# ui-jetson-nano.net
KiCad netlist of a schematic drawn in Altium Designer
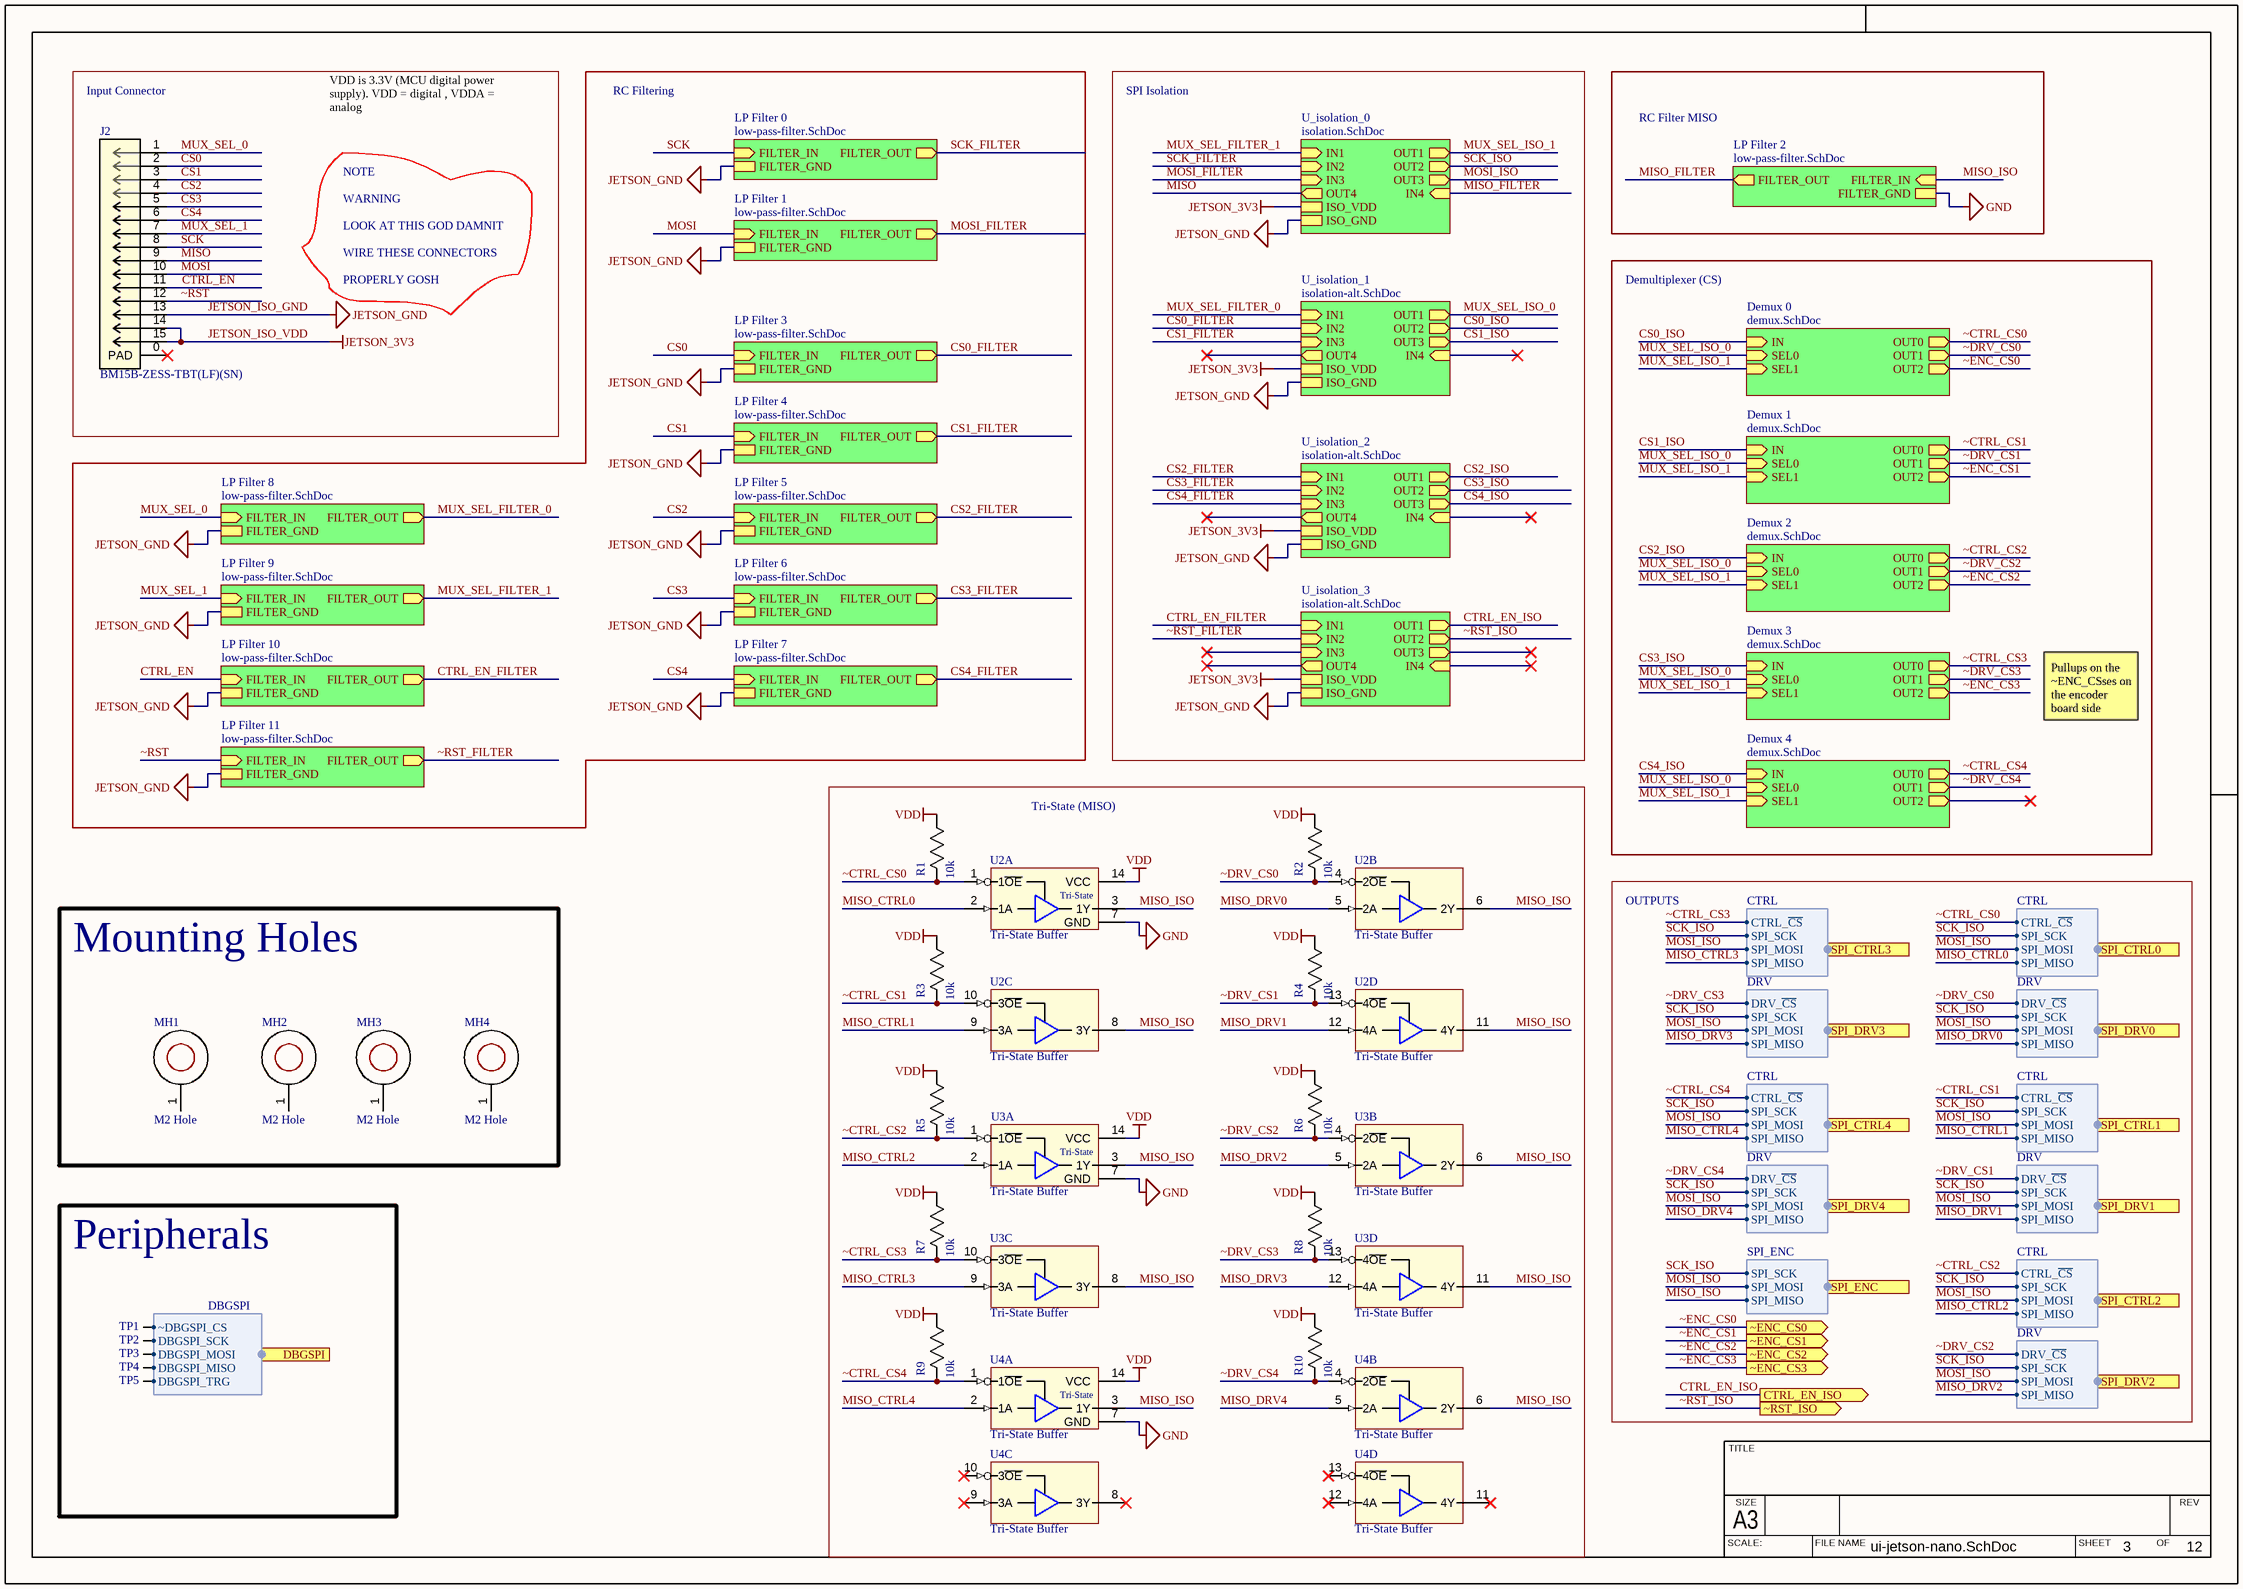
[diagram p0: ui-jetson-nano.SchDoc]

(export (version "E")
  (design (tool "Eeschema 10.0.6"))
  (components
    (comp (ref "J2")
      (value "BM15B-ZESS-TBT(LF)(SN)")
      (footprint "JST ZE SMT 15POS")
      (description "CONN HEADER VERT SMD 15POS ZE")
      (fields (field (name "PART NUMBER") "CN 15POS JST ZE SMT"))
      (libsource (lib "Connector_Library") (part "CN 15POS JST ZE SMT"))
    )
    (comp (ref "MH1")
      (value "M2 Hole")
      (footprint "Mounting Hole M2")
      (description "Standard M2 Mounting Hole for M2 Standoff")
      (fields (field (name "PART NUMBER") "MOUNTING HOLE M2"))
      (libsource (lib "IC_Library") (part "MOUNTING HOLE M2"))
    )
    (comp (ref "MH2")
      (value "M2 Hole")
      (footprint "Mounting Hole M2")
      (description "Standard M2 Mounting Hole for M2 Standoff")
      (fields (field (name "PART NUMBER") "MOUNTING HOLE M2"))
      (libsource (lib "IC_Library") (part "MOUNTING HOLE M2"))
    )
    (comp (ref "MH3")
      (value "M2 Hole")
      (footprint "Mounting Hole M2")
      (description "Standard M2 Mounting Hole for M2 Standoff")
      (fields (field (name "PART NUMBER") "MOUNTING HOLE M2"))
      (libsource (lib "IC_Library") (part "MOUNTING HOLE M2"))
    )
    (comp (ref "MH4")
      (value "M2 Hole")
      (footprint "Mounting Hole M2")
      (description "Standard M2 Mounting Hole for M2 Standoff")
      (fields (field (name "PART NUMBER") "MOUNTING HOLE M2"))
      (libsource (lib "IC_Library") (part "MOUNTING HOLE M2"))
    )
    (comp (ref "R1")
      (value "10k")
      (footprint "0603")
      (description "Default Resistor Symbol")
      (fields (field (name "TOLERANCE") "5%") (field (name "PART NUMBER") "RES 10k 1/8W - 1%"))
      (libsource (lib "Resistor_Library") (part "RES_DEFAULT"))
    )
    (comp (ref "R2")
      (value "10k")
      (footprint "0603")
      (description "Default Resistor Symbol")
      (fields (field (name "TOLERANCE") "5%") (field (name "PART NUMBER") "RES 10k 1/8W - 1%"))
      (libsource (lib "Resistor_Library") (part "RES_DEFAULT"))
    )
    (comp (ref "R3")
      (value "10k")
      (footprint "0603")
      (description "Default Resistor Symbol")
      (fields (field (name "TOLERANCE") "5%") (field (name "PART NUMBER") "RES 10k 1/8W - 1%"))
      (libsource (lib "Resistor_Library") (part "RES_DEFAULT"))
    )
    (comp (ref "R4")
      (value "10k")
      (footprint "0603")
      (description "Default Resistor Symbol")
      (fields (field (name "TOLERANCE") "5%") (field (name "PART NUMBER") "RES 10k 1/8W - 1%"))
      (libsource (lib "Resistor_Library") (part "RES_DEFAULT"))
    )
    (comp (ref "R5")
      (value "10k")
      (footprint "0603")
      (description "Default Resistor Symbol")
      (fields (field (name "TOLERANCE") "5%") (field (name "PART NUMBER") "RES 10k 1/8W - 1%"))
      (libsource (lib "Resistor_Library") (part "RES_DEFAULT"))
    )
    (comp (ref "R6")
      (value "10k")
      (footprint "0603")
      (description "Default Resistor Symbol")
      (fields (field (name "TOLERANCE") "5%") (field (name "PART NUMBER") "RES 10k 1/8W - 1%"))
      (libsource (lib "Resistor_Library") (part "RES_DEFAULT"))
    )
    (comp (ref "R7")
      (value "10k")
      (footprint "0603")
      (description "Default Resistor Symbol")
      (fields (field (name "TOLERANCE") "5%") (field (name "PART NUMBER") "RES 10k 1/8W - 1%"))
      (libsource (lib "Resistor_Library") (part "RES_DEFAULT"))
    )
    (comp (ref "R8")
      (value "10k")
      (footprint "0603")
      (description "Default Resistor Symbol")
      (fields (field (name "TOLERANCE") "5%") (field (name "PART NUMBER") "RES 10k 1/8W - 1%"))
      (libsource (lib "Resistor_Library") (part "RES_DEFAULT"))
    )
    (comp (ref "R9")
      (value "10k")
      (footprint "0603")
      (description "Default Resistor Symbol")
      (fields (field (name "TOLERANCE") "5%") (field (name "PART NUMBER") "RES 10k 1/8W - 1%"))
      (libsource (lib "Resistor_Library") (part "RES_DEFAULT"))
    )
    (comp (ref "R10")
      (value "10k")
      (footprint "0603")
      (description "Default Resistor Symbol")
      (fields (field (name "TOLERANCE") "5%") (field (name "PART NUMBER") "RES 10k 1/8W - 1%"))
      (libsource (lib "Resistor_Library") (part "RES_DEFAULT"))
    )
    (comp (ref "TP1")
      (value "Test Point (Via)")
      (footprint "TP")
      (libsource (lib "IC_Library") (part "Test Point (Via)"))
    )
    (comp (ref "TP2")
      (value "Test Point (Via)")
      (footprint "TP")
      (libsource (lib "IC_Library") (part "Test Point (Via)"))
    )
    (comp (ref "TP3")
      (value "Test Point (Via)")
      (footprint "TP")
      (libsource (lib "IC_Library") (part "Test Point (Via)"))
    )
    (comp (ref "TP4")
      (value "Test Point (Via)")
      (footprint "TP")
      (libsource (lib "IC_Library") (part "Test Point (Via)"))
    )
    (comp (ref "TP5")
      (value "Test Point (Via)")
      (footprint "TP")
      (libsource (lib "IC_Library") (part "Test Point (Via)"))
    )
    (comp (ref "U2")
      (value "Tri-State Buffer")
      (footprint "14-TSSOP")
      (description "Buffer, Non-Inverting 4 Element 1 Bit per Element 3-State Output 14-TSSOP")
      (fields (field (name "PART NUMBER") "SN74LVC125APWR"))
      (libsource (lib "IC_Library") (part "SN74LVC125APWR"))
    )
    (comp (ref "U3")
      (value "Tri-State Buffer")
      (footprint "14-TSSOP")
      (description "Buffer, Non-Inverting 4 Element 1 Bit per Element 3-State Output 14-TSSOP")
      (fields (field (name "PART NUMBER") "SN74LVC125APWR"))
      (libsource (lib "IC_Library") (part "SN74LVC125APWR"))
    )
    (comp (ref "U4")
      (value "Tri-State Buffer")
      (footprint "14-TSSOP")
      (description "Buffer, Non-Inverting 4 Element 1 Bit per Element 3-State Output 14-TSSOP")
      (fields (field (name "PART NUMBER") "SN74LVC125APWR"))
      (libsource (lib "IC_Library") (part "SN74LVC125APWR"))
    )
  )
  (nets
    (net (code "5") (name "/CS0") (class "Default")
      (node (ref "J2") (pin "2") (pinfunction "2_2") (pintype "passive"))
    )
    (net (code "8") (name "/CS1") (class "Default")
      (node (ref "J2") (pin "3") (pinfunction "3_3") (pintype "passive"))
    )
    (net (code "11") (name "/CS2") (class "Default")
      (node (ref "J2") (pin "4") (pinfunction "4_4") (pintype "passive"))
    )
    (net (code "14") (name "/CS3") (class "Default")
      (node (ref "J2") (pin "5") (pinfunction "5_5") (pintype "passive"))
    )
    (net (code "17") (name "/CS4") (class "Default")
      (node (ref "J2") (pin "6") (pinfunction "6_6") (pintype "passive"))
    )
    (net (code "20") (name "/CTRL_EN") (class "Default")
      (node (ref "J2") (pin "11") (pinfunction "11_11") (pintype "passive"))
    )
    (net (code "23") (name "/DBGSPI_MISO") (class "Default")
      (node (ref "TP4") (pin "1") (pinfunction "1_1") (pintype "passive"))
    )
    (net (code "24") (name "/DBGSPI_MOSI") (class "Default")
      (node (ref "TP3") (pin "1") (pinfunction "1_1") (pintype "passive"))
    )
    (net (code "25") (name "/DBGSPI_SCK") (class "Default")
      (node (ref "TP2") (pin "1") (pinfunction "1_1") (pintype "passive"))
    )
    (net (code "26") (name "/DBGSPI_TRG") (class "Default")
      (node (ref "TP5") (pin "1") (pinfunction "1_1") (pintype "passive"))
    )
    (net (code "31") (name "/MISO") (class "Default")
      (node (ref "J2") (pin "9") (pinfunction "9_9") (pintype "passive"))
    )
    (net (code "32") (name "/MISO_CTRL0") (class "Default")
      (node (ref "U2") (pin "2") (pinfunction "1A_2") (pintype "input"))
    )
    (net (code "33") (name "/MISO_CTRL1") (class "Default")
      (node (ref "U2") (pin "9") (pinfunction "3A_9") (pintype "input"))
    )
    (net (code "34") (name "/MISO_CTRL2") (class "Default")
      (node (ref "U3") (pin "2") (pinfunction "1A_2") (pintype "input"))
    )
    (net (code "35") (name "/MISO_CTRL3") (class "Default")
      (node (ref "U3") (pin "9") (pinfunction "3A_9") (pintype "input"))
    )
    (net (code "36") (name "/MISO_CTRL4") (class "Default")
      (node (ref "U4") (pin "2") (pinfunction "1A_2") (pintype "input"))
    )
    (net (code "37") (name "/MISO_DRV0") (class "Default")
      (node (ref "U2") (pin "5") (pinfunction "2A_5") (pintype "input"))
    )
    (net (code "38") (name "/MISO_DRV1") (class "Default")
      (node (ref "U2") (pin "12") (pinfunction "4A_12") (pintype "input"))
    )
    (net (code "39") (name "/MISO_DRV2") (class "Default")
      (node (ref "U3") (pin "5") (pinfunction "2A_5") (pintype "input"))
    )
    (net (code "40") (name "/MISO_DRV3") (class "Default")
      (node (ref "U3") (pin "12") (pinfunction "4A_12") (pintype "input"))
    )
    (net (code "41") (name "/MISO_DRV4") (class "Default")
      (node (ref "U4") (pin "5") (pinfunction "2A_5") (pintype "input"))
    )
    (net (code "43") (name "/MISO_ISO") (class "Default")
      (node (ref "U2") (pin "11") (pinfunction "4Y_11") (pintype "passive"))
      (node (ref "U2") (pin "3") (pinfunction "1Y_3") (pintype "passive"))
      (node (ref "U2") (pin "6") (pinfunction "2Y_6") (pintype "passive"))
      (node (ref "U2") (pin "8") (pinfunction "3Y_8") (pintype "passive"))
      (node (ref "U3") (pin "11") (pinfunction "4Y_11") (pintype "passive"))
      (node (ref "U3") (pin "3") (pinfunction "1Y_3") (pintype "passive"))
      (node (ref "U3") (pin "6") (pinfunction "2Y_6") (pintype "passive"))
      (node (ref "U3") (pin "8") (pinfunction "3Y_8") (pintype "passive"))
      (node (ref "U4") (pin "3") (pinfunction "1Y_3") (pintype "passive"))
      (node (ref "U4") (pin "6") (pinfunction "2Y_6") (pintype "passive"))
    )
    (net (code "44") (name "/MOSI") (class "Default")
      (node (ref "J2") (pin "10") (pinfunction "10_10") (pintype "passive"))
    )
    (net (code "47") (name "/MUX_SEL_0") (class "Default")
      (node (ref "J2") (pin "1") (pinfunction "1_1") (pintype "passive"))
    )
    (net (code "48") (name "/MUX_SEL_1") (class "Default")
      (node (ref "J2") (pin "7") (pinfunction "7_7") (pintype "passive"))
    )
    (net (code "58") (name "/SCK") (class "Default")
      (node (ref "J2") (pin "8") (pinfunction "8_8") (pintype "passive"))
    )
    (net (code "65") (name "/~CTRL_CS0") (class "Default")
      (node (ref "R1") (pin "2") (pinfunction "R2_2") (pintype "passive"))
      (node (ref "U2") (pin "1") (pinfunction "1~{OE}_1") (pintype "input"))
    )
    (net (code "66") (name "/~CTRL_CS1") (class "Default")
      (node (ref "R3") (pin "2") (pinfunction "R2_2") (pintype "passive"))
      (node (ref "U2") (pin "10") (pinfunction "3~{OE}_10") (pintype "input"))
    )
    (net (code "67") (name "/~CTRL_CS2") (class "Default")
      (node (ref "R5") (pin "2") (pinfunction "R2_2") (pintype "passive"))
      (node (ref "U3") (pin "1") (pinfunction "1~{OE}_1") (pintype "input"))
    )
    (net (code "68") (name "/~CTRL_CS3") (class "Default")
      (node (ref "R7") (pin "2") (pinfunction "R2_2") (pintype "passive"))
      (node (ref "U3") (pin "10") (pinfunction "3~{OE}_10") (pintype "input"))
    )
    (net (code "69") (name "/~CTRL_CS4") (class "Default")
      (node (ref "R9") (pin "2") (pinfunction "R2_2") (pintype "passive"))
      (node (ref "U4") (pin "1") (pinfunction "1~{OE}_1") (pintype "input"))
    )
    (net (code "70") (name "/~DBGSPI_CS") (class "Default")
      (node (ref "TP1") (pin "1") (pinfunction "1_1") (pintype "passive"))
    )
    (net (code "71") (name "/~DRV_CS0") (class "Default")
      (node (ref "R2") (pin "2") (pinfunction "R2_2") (pintype "passive"))
      (node (ref "U2") (pin "4") (pinfunction "2~{OE}_4") (pintype "input"))
    )
    (net (code "72") (name "/~DRV_CS1") (class "Default")
      (node (ref "R4") (pin "2") (pinfunction "R2_2") (pintype "passive"))
      (node (ref "U2") (pin "13") (pinfunction "4~{OE}_13") (pintype "input"))
    )
    (net (code "73") (name "/~DRV_CS2") (class "Default")
      (node (ref "R6") (pin "2") (pinfunction "R2_2") (pintype "passive"))
      (node (ref "U3") (pin "4") (pinfunction "2~{OE}_4") (pintype "input"))
    )
    (net (code "74") (name "/~DRV_CS3") (class "Default")
      (node (ref "R8") (pin "2") (pinfunction "R2_2") (pintype "passive"))
      (node (ref "U3") (pin "13") (pinfunction "4~{OE}_13") (pintype "input"))
    )
    (net (code "75") (name "/~DRV_CS4") (class "Default")
      (node (ref "R10") (pin "2") (pinfunction "R2_2") (pintype "passive"))
      (node (ref "U4") (pin "4") (pinfunction "2~{OE}_4") (pintype "input"))
    )
    (net (code "80") (name "/~RST") (class "Default")
      (node (ref "J2") (pin "12") (pinfunction "12_12") (pintype "passive"))
    )
    (net (code "83") (name "GND") (class "Default")
      (node (ref "U2") (pin "7") (pinfunction "GND_7") (pintype "passive"))
      (node (ref "U3") (pin "7") (pinfunction "GND_7") (pintype "passive"))
      (node (ref "U4") (pin "7") (pinfunction "GND_7") (pintype "passive"))
    )
    (net (code "84") (name "JETSON_3V3") (class "Default")
      (node (ref "J2") (pin "14") (pinfunction "14_14") (pintype "passive"))
      (node (ref "J2") (pin "15") (pinfunction "15_15") (pintype "passive"))
    )
    (net (code "85") (name "JETSON_GND") (class "Default")
      (node (ref "J2") (pin "13") (pinfunction "13_13") (pintype "passive"))
    )
    (net (code "86") (name "VDD") (class "Default")
      (node (ref "R1") (pin "1") (pinfunction "R1_1") (pintype "passive"))
      (node (ref "R10") (pin "1") (pinfunction "R1_1") (pintype "passive"))
      (node (ref "R2") (pin "1") (pinfunction "R1_1") (pintype "passive"))
      (node (ref "R3") (pin "1") (pinfunction "R1_1") (pintype "passive"))
      (node (ref "R4") (pin "1") (pinfunction "R1_1") (pintype "passive"))
      (node (ref "R5") (pin "1") (pinfunction "R1_1") (pintype "passive"))
      (node (ref "R6") (pin "1") (pinfunction "R1_1") (pintype "passive"))
      (node (ref "R7") (pin "1") (pinfunction "R1_1") (pintype "passive"))
      (node (ref "R8") (pin "1") (pinfunction "R1_1") (pintype "passive"))
      (node (ref "R9") (pin "1") (pinfunction "R1_1") (pintype "passive"))
      (node (ref "U2") (pin "14") (pinfunction "VCC_14") (pintype "passive"))
      (node (ref "U3") (pin "14") (pinfunction "VCC_14") (pintype "passive"))
      (node (ref "U4") (pin "14") (pinfunction "VCC_14") (pintype "passive"))
    )
    (net (code "87") (name "unconnected-(J2-PAD-Pad0)") (class "Default")
      (node (ref "J2") (pin "0") (pinfunction "PAD_0") (pintype "passive+no_connect"))
    )
    (net (code "88") (name "unconnected-(MH1-Pad1)") (class "Default")
      (node (ref "MH1") (pin "1") (pinfunction "1_1") (pintype "passive"))
    )
    (net (code "89") (name "unconnected-(MH2-Pad1)") (class "Default")
      (node (ref "MH2") (pin "1") (pinfunction "1_1") (pintype "passive"))
    )
    (net (code "90") (name "unconnected-(MH3-Pad1)") (class "Default")
      (node (ref "MH3") (pin "1") (pinfunction "1_1") (pintype "passive"))
    )
    (net (code "91") (name "unconnected-(MH4-Pad1)") (class "Default")
      (node (ref "MH4") (pin "1") (pinfunction "1_1") (pintype "passive"))
    )
    (net (code "92") (name "unconnected-(U4C-3A-Pad9)") (class "Default")
      (node (ref "U4") (pin "9") (pinfunction "3A_9") (pintype "input+no_connect"))
    )
    (net (code "93") (name "unconnected-(U4C-3Y-Pad8)") (class "Default")
      (node (ref "U4") (pin "8") (pinfunction "3Y_8") (pintype "passive+no_connect"))
    )
    (net (code "94") (name "unconnected-(U4C-3~{OE}-Pad10)") (class "Default")
      (node (ref "U4") (pin "10") (pinfunction "3~{OE}_10") (pintype "input+no_connect"))
    )
    (net (code "95") (name "unconnected-(U4D-4A-Pad12)") (class "Default")
      (node (ref "U4") (pin "12") (pinfunction "4A_12") (pintype "input+no_connect"))
    )
    (net (code "96") (name "unconnected-(U4D-4Y-Pad11)") (class "Default")
      (node (ref "U4") (pin "11") (pinfunction "4Y_11") (pintype "passive+no_connect"))
    )
    (net (code "97") (name "unconnected-(U4D-4~{OE}-Pad13)") (class "Default")
      (node (ref "U4") (pin "13") (pinfunction "4~{OE}_13") (pintype "input+no_connect"))
    )
  )
)
